# SENSORS.net
KiCad netlist of a schematic drawn in Altium Designer
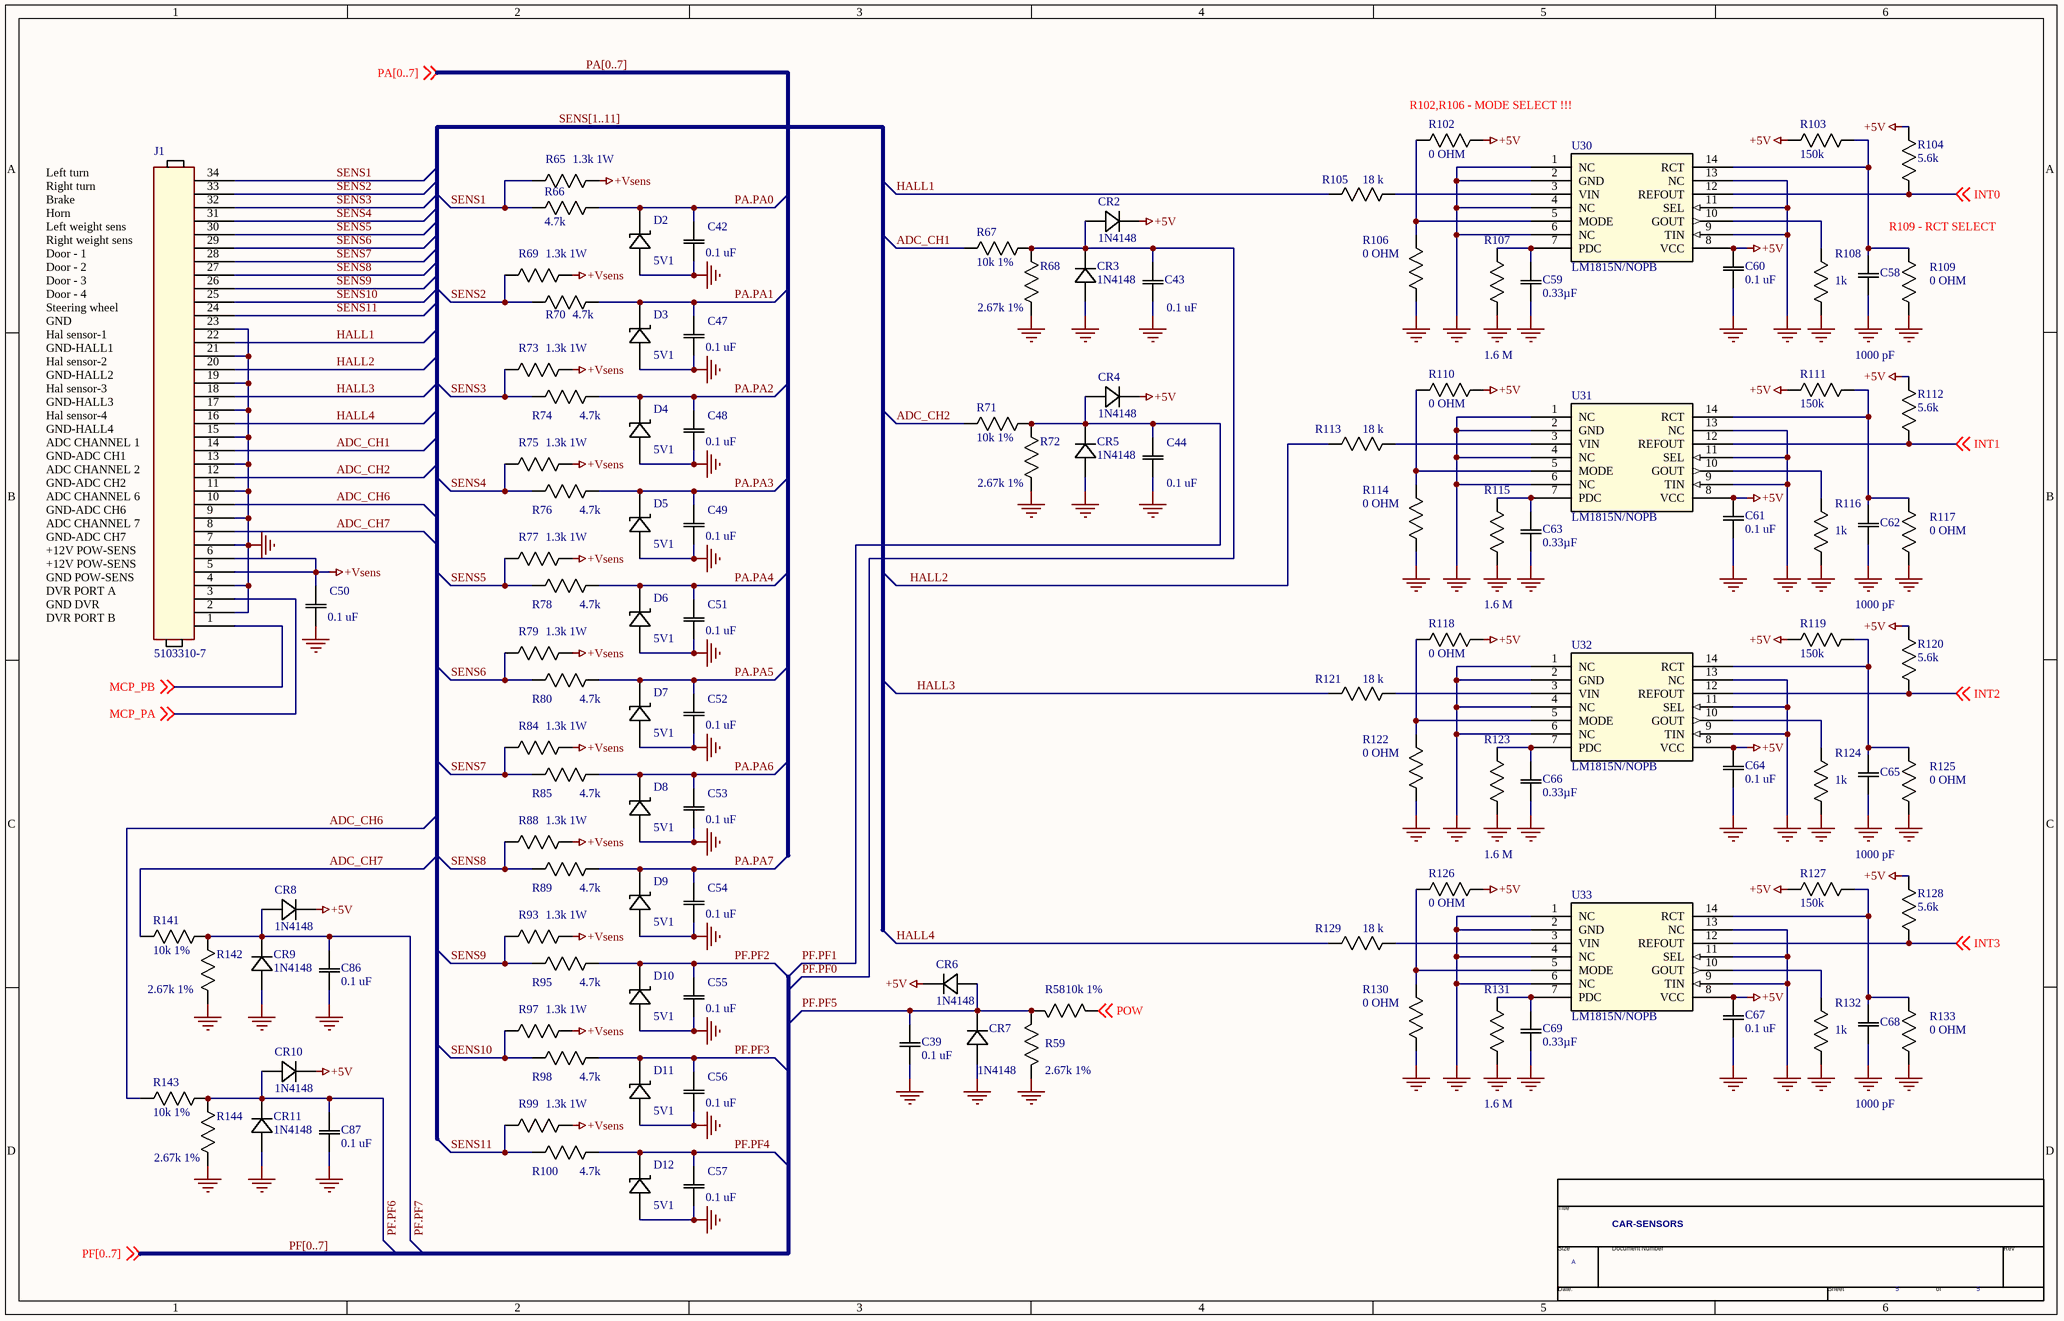
[diagram p0: SENSORS.SchDoc]

(export (version "E")
  (design (tool "Eeschema 10.0.6"))
  (components
    (comp (ref "C39")
      (value "0.1 uF")
      (footprint "SR20")
      (description "0.1µF ±10% 100V Ceramic Capacitor X7R Radial")
      (fields (field (name "MANUFACTURER_PART_NUMBER") "C320C104K1R5TA7301"))
      (libsource (lib "Discrete") (part "CAP RADIAL 2.54"))
    )
    (comp (ref "C42")
      (value "0.1 uF")
      (footprint "SR20")
      (description "0.1µF ±10% 100V Ceramic Capacitor X7R Radial")
      (fields (field (name "MANUFACTURER_PART_NUMBER") "C320C104K1R5TA7301"))
      (libsource (lib "Discrete") (part "CAP RADIAL 2.54"))
    )
    (comp (ref "C43")
      (value "0.1 uF")
      (footprint "SR20")
      (description "0.1µF ±10% 100V Ceramic Capacitor X7R Radial")
      (fields (field (name "MANUFACTURER_PART_NUMBER") "C320C104K1R5TA7301"))
      (libsource (lib "Discrete") (part "CAP RADIAL 2.54"))
    )
    (comp (ref "C44")
      (value "0.1 uF")
      (footprint "SR20")
      (description "0.1µF ±10% 100V Ceramic Capacitor X7R Radial")
      (fields (field (name "MANUFACTURER_PART_NUMBER") "C320C104K1R5TA7301"))
      (libsource (lib "Discrete") (part "CAP RADIAL 2.54"))
    )
    (comp (ref "C47")
      (value "0.1 uF")
      (footprint "SR20")
      (description "0.1µF ±10% 100V Ceramic Capacitor X7R Radial")
      (fields (field (name "MANUFACTURER_PART_NUMBER") "C320C104K1R5TA7301"))
      (libsource (lib "Discrete") (part "CAP RADIAL 2.54"))
    )
    (comp (ref "C48")
      (value "0.1 uF")
      (footprint "SR20")
      (description "0.1µF ±10% 100V Ceramic Capacitor X7R Radial")
      (fields (field (name "MANUFACTURER_PART_NUMBER") "C320C104K1R5TA7301"))
      (libsource (lib "Discrete") (part "CAP RADIAL 2.54"))
    )
    (comp (ref "C49")
      (value "0.1 uF")
      (footprint "SR20")
      (description "0.1µF ±10% 100V Ceramic Capacitor X7R Radial")
      (fields (field (name "MANUFACTURER_PART_NUMBER") "C320C104K1R5TA7301"))
      (libsource (lib "Discrete") (part "CAP RADIAL 2.54"))
    )
    (comp (ref "C50")
      (value "0.1 uF")
      (footprint "SR20")
      (description "0.1µF ±10% 100V Ceramic Capacitor X7R Radial")
      (fields (field (name "MANUFACTURER_PART_NUMBER") "C320C104K1R5TA7301"))
      (libsource (lib "Discrete") (part "CAP RADIAL 2.54"))
    )
    (comp (ref "C51")
      (value "0.1 uF")
      (footprint "SR20")
      (description "0.1µF ±10% 100V Ceramic Capacitor X7R Radial")
      (fields (field (name "MANUFACTURER_PART_NUMBER") "C320C104K1R5TA7301"))
      (libsource (lib "Discrete") (part "CAP RADIAL 2.54"))
    )
    (comp (ref "C52")
      (value "0.1 uF")
      (footprint "SR20")
      (description "0.1µF ±10% 100V Ceramic Capacitor X7R Radial")
      (fields (field (name "MANUFACTURER_PART_NUMBER") "C320C104K1R5TA7301"))
      (libsource (lib "Discrete") (part "CAP RADIAL 2.54"))
    )
    (comp (ref "C53")
      (value "0.1 uF")
      (footprint "SR20")
      (description "0.1µF ±10% 100V Ceramic Capacitor X7R Radial")
      (fields (field (name "MANUFACTURER_PART_NUMBER") "C320C104K1R5TA7301"))
      (libsource (lib "Discrete") (part "CAP RADIAL 2.54"))
    )
    (comp (ref "C54")
      (value "0.1 uF")
      (footprint "SR20")
      (description "0.1µF ±10% 100V Ceramic Capacitor X7R Radial")
      (fields (field (name "MANUFACTURER_PART_NUMBER") "C320C104K1R5TA7301"))
      (libsource (lib "Discrete") (part "CAP RADIAL 2.54"))
    )
    (comp (ref "C55")
      (value "0.1 uF")
      (footprint "SR20")
      (description "0.1µF ±10% 100V Ceramic Capacitor X7R Radial")
      (fields (field (name "MANUFACTURER_PART_NUMBER") "C320C104K1R5TA7301"))
      (libsource (lib "Discrete") (part "CAP RADIAL 2.54"))
    )
    (comp (ref "C56")
      (value "0.1 uF")
      (footprint "SR20")
      (description "0.1µF ±10% 100V Ceramic Capacitor X7R Radial")
      (fields (field (name "MANUFACTURER_PART_NUMBER") "C320C104K1R5TA7301"))
      (libsource (lib "Discrete") (part "CAP RADIAL 2.54"))
    )
    (comp (ref "C57")
      (value "0.1 uF")
      (footprint "SR20")
      (description "0.1µF ±10% 100V Ceramic Capacitor X7R Radial")
      (fields (field (name "MANUFACTURER_PART_NUMBER") "C320C104K1R5TA7301"))
      (libsource (lib "Discrete") (part "CAP RADIAL 2.54"))
    )
    (comp (ref "C58")
      (value "1000 pF")
      (footprint "SR20")
      (description "CAP CER 1000PF 50V X7R RADIAL")
      (fields (field (name "MANUFACTURER_PART_NUMBER") "C315C102K5R5TA7301"))
      (libsource (lib "Discrete") (part "CAP RADIAL 2.54"))
    )
    (comp (ref "C59")
      (value "0.33µF")
      (footprint "SR20")
      (description "CAP CER 0.33UF 50V X8R RADIAL")
      (fields (field (name "MANUFACTURER_PART_NUMBER") "AR205F334K4R"))
      (libsource (lib "Discrete") (part "CAP RADIAL 2.54"))
    )
    (comp (ref "C60")
      (value "0.1 uF")
      (footprint "SR20")
      (description "0.1µF ±10% 100V Ceramic Capacitor X7R Radial")
      (fields (field (name "MANUFACTURER_PART_NUMBER") "C320C104K1R5TA7301"))
      (libsource (lib "Discrete") (part "CAP RADIAL 2.54"))
    )
    (comp (ref "C61")
      (value "0.1 uF")
      (footprint "SR20")
      (description "0.1µF ±10% 100V Ceramic Capacitor X7R Radial")
      (fields (field (name "MANUFACTURER_PART_NUMBER") "C320C104K1R5TA7301"))
      (libsource (lib "Discrete") (part "CAP RADIAL 2.54"))
    )
    (comp (ref "C62")
      (value "1000 pF")
      (footprint "SR20")
      (description "CAP CER 1000PF 50V X7R RADIAL")
      (fields (field (name "MANUFACTURER_PART_NUMBER") "C315C102K5R5TA7301"))
      (libsource (lib "Discrete") (part "CAP RADIAL 2.54"))
    )
    (comp (ref "C63")
      (value "0.33µF")
      (footprint "SR20")
      (description "CAP CER 0.33UF 50V X8R RADIAL")
      (fields (field (name "MANUFACTURER_PART_NUMBER") "AR205F334K4R"))
      (libsource (lib "Discrete") (part "CAP RADIAL 2.54"))
    )
    (comp (ref "C64")
      (value "0.1 uF")
      (footprint "SR20")
      (description "0.1µF ±10% 100V Ceramic Capacitor X7R Radial")
      (fields (field (name "MANUFACTURER_PART_NUMBER") "C320C104K1R5TA7301"))
      (libsource (lib "Discrete") (part "CAP RADIAL 2.54"))
    )
    (comp (ref "C65")
      (value "1000 pF")
      (footprint "SR20")
      (description "CAP CER 1000PF 50V X7R RADIAL")
      (fields (field (name "MANUFACTURER_PART_NUMBER") "C315C102K5R5TA7301"))
      (libsource (lib "Discrete") (part "CAP RADIAL 2.54"))
    )
    (comp (ref "C66")
      (value "0.33µF")
      (footprint "SR20")
      (description "CAP CER 0.33UF 50V X8R RADIAL")
      (fields (field (name "MANUFACTURER_PART_NUMBER") "AR205F334K4R"))
      (libsource (lib "Discrete") (part "CAP RADIAL 2.54"))
    )
    (comp (ref "C67")
      (value "0.1 uF")
      (footprint "SR20")
      (description "0.1µF ±10% 100V Ceramic Capacitor X7R Radial")
      (fields (field (name "MANUFACTURER_PART_NUMBER") "C320C104K1R5TA7301"))
      (libsource (lib "Discrete") (part "CAP RADIAL 2.54"))
    )
    (comp (ref "C68")
      (value "1000 pF")
      (footprint "SR20")
      (description "CAP CER 1000PF 50V X7R RADIAL")
      (fields (field (name "MANUFACTURER_PART_NUMBER") "C315C102K5R5TA7301"))
      (libsource (lib "Discrete") (part "CAP RADIAL 2.54"))
    )
    (comp (ref "C69")
      (value "0.33µF")
      (footprint "SR20")
      (description "CAP CER 0.33UF 50V X8R RADIAL")
      (fields (field (name "MANUFACTURER_PART_NUMBER") "AR205F334K4R"))
      (libsource (lib "Discrete") (part "CAP RADIAL 2.54"))
    )
    (comp (ref "C86")
      (value "0.1 uF")
      (footprint "SR20")
      (description "0.1µF ±10% 100V Ceramic Capacitor X7R Radial")
      (fields (field (name "MANUFACTURER_PART_NUMBER") "C320C104K1R5TA7301"))
      (libsource (lib "Discrete") (part "CAP RADIAL 2.54"))
    )
    (comp (ref "C87")
      (value "0.1 uF")
      (footprint "SR20")
      (description "0.1µF ±10% 100V Ceramic Capacitor X7R Radial")
      (fields (field (name "MANUFACTURER_PART_NUMBER") "C320C104K1R5TA7301"))
      (libsource (lib "Discrete") (part "CAP RADIAL 2.54"))
    )
    (comp (ref "CR2")
      (value "1N4148")
      (footprint "DO35")
      (description "Imported")
      (fields (field (name "COPYRIGHT") "Copyright (C) 2016 Accelerated Designs. All rights reserved"))
      (libsource (lib "Discrete") (part "1N4148"))
    )
    (comp (ref "CR3")
      (value "1N4148")
      (footprint "DO35")
      (description "Imported")
      (fields (field (name "COPYRIGHT") "Copyright (C) 2016 Accelerated Designs. All rights reserved"))
      (libsource (lib "Discrete") (part "1N4148"))
    )
    (comp (ref "CR4")
      (value "1N4148")
      (footprint "DO35")
      (description "Imported")
      (fields (field (name "COPYRIGHT") "Copyright (C) 2016 Accelerated Designs. All rights reserved"))
      (libsource (lib "Discrete") (part "1N4148"))
    )
    (comp (ref "CR5")
      (value "1N4148")
      (footprint "DO35")
      (description "Imported")
      (fields (field (name "COPYRIGHT") "Copyright (C) 2016 Accelerated Designs. All rights reserved"))
      (libsource (lib "Discrete") (part "1N4148"))
    )
    (comp (ref "CR6")
      (value "1N4148")
      (footprint "DO35")
      (description "Imported")
      (fields (field (name "COPYRIGHT") "Copyright (C) 2016 Accelerated Designs. All rights reserved"))
      (libsource (lib "Discrete") (part "1N4148"))
    )
    (comp (ref "CR7")
      (value "1N4148")
      (footprint "DO35")
      (description "Imported")
      (fields (field (name "COPYRIGHT") "Copyright (C) 2016 Accelerated Designs. All rights reserved"))
      (libsource (lib "Discrete") (part "1N4148"))
    )
    (comp (ref "CR8")
      (value "1N4148")
      (footprint "DO35")
      (description "Imported")
      (fields (field (name "COPYRIGHT") "Copyright (C) 2016 Accelerated Designs. All rights reserved"))
      (libsource (lib "Discrete") (part "1N4148"))
    )
    (comp (ref "CR9")
      (value "1N4148")
      (footprint "DO35")
      (description "Imported")
      (fields (field (name "COPYRIGHT") "Copyright (C) 2016 Accelerated Designs. All rights reserved"))
      (libsource (lib "Discrete") (part "1N4148"))
    )
    (comp (ref "CR10")
      (value "1N4148")
      (footprint "DO35")
      (description "Imported")
      (fields (field (name "COPYRIGHT") "Copyright (C) 2016 Accelerated Designs. All rights reserved"))
      (libsource (lib "Discrete") (part "1N4148"))
    )
    (comp (ref "CR11")
      (value "1N4148")
      (footprint "DO35")
      (description "Imported")
      (fields (field (name "COPYRIGHT") "Copyright (C) 2016 Accelerated Designs. All rights reserved"))
      (libsource (lib "Discrete") (part "1N4148"))
    )
    (comp (ref "D2")
      (value "5V1")
      (footprint "DO35")
      (description "DIODE ZENER 5.1V 500MW DO35")
      (fields (field (name "MANUFACTURER_PART_NUMBER") "1N5231B"))
      (libsource (lib "Discrete") (part "ZENNER DO-35"))
    )
    (comp (ref "D3")
      (value "5V1")
      (footprint "DO35")
      (description "DIODE ZENER 5.1V 500MW DO35")
      (fields (field (name "MANUFACTURER_PART_NUMBER") "1N5231B"))
      (libsource (lib "Discrete") (part "ZENNER DO-35"))
    )
    (comp (ref "D4")
      (value "5V1")
      (footprint "DO35")
      (description "DIODE ZENER 5.1V 500MW DO35")
      (fields (field (name "MANUFACTURER_PART_NUMBER") "1N5231B"))
      (libsource (lib "Discrete") (part "ZENNER DO-35"))
    )
    (comp (ref "D5")
      (value "5V1")
      (footprint "DO35")
      (description "DIODE ZENER 5.1V 500MW DO35")
      (fields (field (name "MANUFACTURER_PART_NUMBER") "1N5231B"))
      (libsource (lib "Discrete") (part "ZENNER DO-35"))
    )
    (comp (ref "D6")
      (value "5V1")
      (footprint "DO35")
      (description "DIODE ZENER 5.1V 500MW DO35")
      (fields (field (name "MANUFACTURER_PART_NUMBER") "1N5231B"))
      (libsource (lib "Discrete") (part "ZENNER DO-35"))
    )
    (comp (ref "D7")
      (value "5V1")
      (footprint "DO35")
      (description "DIODE ZENER 5.1V 500MW DO35")
      (fields (field (name "MANUFACTURER_PART_NUMBER") "1N5231B"))
      (libsource (lib "Discrete") (part "ZENNER DO-35"))
    )
    (comp (ref "D8")
      (value "5V1")
      (footprint "DO35")
      (description "DIODE ZENER 5.1V 500MW DO35")
      (fields (field (name "MANUFACTURER_PART_NUMBER") "1N5231B"))
      (libsource (lib "Discrete") (part "ZENNER DO-35"))
    )
    (comp (ref "D9")
      (value "5V1")
      (footprint "DO35")
      (description "DIODE ZENER 5.1V 500MW DO35")
      (fields (field (name "MANUFACTURER_PART_NUMBER") "1N5231B"))
      (libsource (lib "Discrete") (part "ZENNER DO-35"))
    )
    (comp (ref "D10")
      (value "5V1")
      (footprint "DO35")
      (description "DIODE ZENER 5.1V 500MW DO35")
      (fields (field (name "MANUFACTURER_PART_NUMBER") "1N5231B"))
      (libsource (lib "Discrete") (part "ZENNER DO-35"))
    )
    (comp (ref "D11")
      (value "5V1")
      (footprint "DO35")
      (description "DIODE ZENER 5.1V 500MW DO35")
      (fields (field (name "MANUFACTURER_PART_NUMBER") "1N5231B"))
      (libsource (lib "Discrete") (part "ZENNER DO-35"))
    )
    (comp (ref "D12")
      (value "5V1")
      (footprint "DO35")
      (description "DIODE ZENER 5.1V 500MW DO35")
      (fields (field (name "MANUFACTURER_PART_NUMBER") "1N5231B"))
      (libsource (lib "Discrete") (part "ZENNER DO-35"))
    )
    (comp (ref "J1")
      (value "5103310-7")
      (footprint "*TYCO_5103310-7")
      (description "A/L LOW PRO HDR 34P RA BLACK")
      (libsource (lib "Connectors") (part "5103310-7"))
    )
    (comp (ref "R58")
      (value "10k 1%")
      (footprint "RES AXIAL 1/6W")
      (description "RES 10K OHM 1/8W 1% AXIAL")
      (fields (field (name "MANUFACTURER_PART_NUMBER") "RNF18FTD10K0"))
      (libsource (lib "Discrete") (part "Resistor Axial  1/6W"))
    )
    (comp (ref "R59")
      (value "2.67k 1%")
      (footprint "YAG_MF25")
      (description "RES 2.67K OHM 1/4W 1% AXIAL")
      (fields (field (name "MANUFACTURER_PART_NUMBER") "MFR-25FBF52-2K67"))
      (libsource (lib "Discrete") (part "Resistor Axial  1/4W"))
    )
    (comp (ref "R65")
      (value "1.3k 1W")
      (footprint "YAG_FMP100")
      (description "RES 1.3K OHM 1W 5% AXIAL")
      (fields (field (name "MANUFACTURER_PART_NUMBER") "RSF100JB-73-1K3"))
      (libsource (lib "Discrete") (part "Resistor Axial  1W"))
    )
    (comp (ref "R66")
      (value "4.7k")
      (footprint "RES AXIAL 1/6W")
      (description "RES 4.7K OHM 1/6W 5% AXIAL")
      (fields (field (name "MANUFACTURER_PART_NUMBER") "CFR-12JB-52-4K7"))
      (libsource (lib "Discrete") (part "Resistor Axial  1/6W"))
    )
    (comp (ref "R67")
      (value "10k 1%")
      (footprint "RES AXIAL 1/6W")
      (description "RES 10K OHM 1/8W 1% AXIAL")
      (fields (field (name "MANUFACTURER_PART_NUMBER") "RNF18FTD10K0"))
      (libsource (lib "Discrete") (part "Resistor Axial  1/6W"))
    )
    (comp (ref "R68")
      (value "2.67k 1%")
      (footprint "YAG_MF25")
      (description "RES 2.67K OHM 1/4W 1% AXIAL")
      (fields (field (name "MANUFACTURER_PART_NUMBER") "MFR-25FBF52-2K67"))
      (libsource (lib "Discrete") (part "Resistor Axial  1/4W"))
    )
    (comp (ref "R69")
      (value "1.3k 1W")
      (footprint "YAG_FMP100")
      (description "RES 1.3K OHM 1W 5% AXIAL")
      (fields (field (name "MANUFACTURER_PART_NUMBER") "RSF100JB-73-1K3"))
      (libsource (lib "Discrete") (part "Resistor Axial  1W"))
    )
    (comp (ref "R70")
      (value "4.7k")
      (footprint "RES AXIAL 1/6W")
      (description "RES 4.7K OHM 1/6W 5% AXIAL")
      (fields (field (name "MANUFACTURER_PART_NUMBER") "CFR-12JB-52-4K7"))
      (libsource (lib "Discrete") (part "Resistor Axial  1/6W"))
    )
    (comp (ref "R71")
      (value "10k 1%")
      (footprint "RES AXIAL 1/6W")
      (description "RES 10K OHM 1/8W 1% AXIAL")
      (fields (field (name "MANUFACTURER_PART_NUMBER") "RNF18FTD10K0"))
      (libsource (lib "Discrete") (part "Resistor Axial  1/6W"))
    )
    (comp (ref "R72")
      (value "2.67k 1%")
      (footprint "YAG_MF25")
      (description "RES 2.67K OHM 1/4W 1% AXIAL")
      (fields (field (name "MANUFACTURER_PART_NUMBER") "MFR-25FBF52-2K67"))
      (libsource (lib "Discrete") (part "Resistor Axial  1/4W"))
    )
    (comp (ref "R73")
      (value "1.3k 1W")
      (footprint "YAG_FMP100")
      (description "RES 1.3K OHM 1W 5% AXIAL")
      (fields (field (name "MANUFACTURER_PART_NUMBER") "RSF100JB-73-1K3"))
      (libsource (lib "Discrete") (part "Resistor Axial  1W"))
    )
    (comp (ref "R74")
      (value "4.7k")
      (footprint "RES AXIAL 1/6W")
      (description "RES 4.7K OHM 1/6W 5% AXIAL")
      (fields (field (name "MANUFACTURER_PART_NUMBER") "CFR-12JB-52-4K7"))
      (libsource (lib "Discrete") (part "Resistor Axial  1/6W"))
    )
    (comp (ref "R75")
      (value "1.3k 1W")
      (footprint "YAG_FMP100")
      (description "RES 1.3K OHM 1W 5% AXIAL")
      (fields (field (name "MANUFACTURER_PART_NUMBER") "RSF100JB-73-1K3"))
      (libsource (lib "Discrete") (part "Resistor Axial  1W"))
    )
    (comp (ref "R76")
      (value "4.7k")
      (footprint "RES AXIAL 1/6W")
      (description "RES 4.7K OHM 1/6W 5% AXIAL")
      (fields (field (name "MANUFACTURER_PART_NUMBER") "CFR-12JB-52-4K7"))
      (libsource (lib "Discrete") (part "Resistor Axial  1/6W"))
    )
    (comp (ref "R77")
      (value "1.3k 1W")
      (footprint "YAG_FMP100")
      (description "RES 1.3K OHM 1W 5% AXIAL")
      (fields (field (name "MANUFACTURER_PART_NUMBER") "RSF100JB-73-1K3"))
      (libsource (lib "Discrete") (part "Resistor Axial  1W"))
    )
    (comp (ref "R78")
      (value "4.7k")
      (footprint "RES AXIAL 1/6W")
      (description "RES 4.7K OHM 1/6W 5% AXIAL")
      (fields (field (name "MANUFACTURER_PART_NUMBER") "CFR-12JB-52-4K7"))
      (libsource (lib "Discrete") (part "Resistor Axial  1/6W"))
    )
    (comp (ref "R79")
      (value "1.3k 1W")
      (footprint "YAG_FMP100")
      (description "RES 1.3K OHM 1W 5% AXIAL")
      (fields (field (name "MANUFACTURER_PART_NUMBER") "RSF100JB-73-1K3"))
      (libsource (lib "Discrete") (part "Resistor Axial  1W"))
    )
    (comp (ref "R80")
      (value "4.7k")
      (footprint "RES AXIAL 1/6W")
      (description "RES 4.7K OHM 1/6W 5% AXIAL")
      (fields (field (name "MANUFACTURER_PART_NUMBER") "CFR-12JB-52-4K7"))
      (libsource (lib "Discrete") (part "Resistor Axial  1/6W"))
    )
    (comp (ref "R84")
      (value "1.3k 1W")
      (footprint "YAG_FMP100")
      (description "RES 1.3K OHM 1W 5% AXIAL")
      (fields (field (name "MANUFACTURER_PART_NUMBER") "RSF100JB-73-1K3"))
      (libsource (lib "Discrete") (part "Resistor Axial  1W"))
    )
    (comp (ref "R85")
      (value "4.7k")
      (footprint "RES AXIAL 1/6W")
      (description "RES 4.7K OHM 1/6W 5% AXIAL")
      (fields (field (name "MANUFACTURER_PART_NUMBER") "CFR-12JB-52-4K7"))
      (libsource (lib "Discrete") (part "Resistor Axial  1/6W"))
    )
    (comp (ref "R88")
      (value "1.3k 1W")
      (footprint "YAG_FMP100")
      (description "RES 1.3K OHM 1W 5% AXIAL")
      (fields (field (name "MANUFACTURER_PART_NUMBER") "RSF100JB-73-1K3"))
      (libsource (lib "Discrete") (part "Resistor Axial  1W"))
    )
    (comp (ref "R89")
      (value "4.7k")
      (footprint "RES AXIAL 1/6W")
      (description "RES 4.7K OHM 1/6W 5% AXIAL")
      (fields (field (name "MANUFACTURER_PART_NUMBER") "CFR-12JB-52-4K7"))
      (libsource (lib "Discrete") (part "Resistor Axial  1/6W"))
    )
    (comp (ref "R93")
      (value "1.3k 1W")
      (footprint "YAG_FMP100")
      (description "RES 1.3K OHM 1W 5% AXIAL")
      (fields (field (name "MANUFACTURER_PART_NUMBER") "RSF100JB-73-1K3"))
      (libsource (lib "Discrete") (part "Resistor Axial  1W"))
    )
    (comp (ref "R95")
      (value "4.7k")
      (footprint "RES AXIAL 1/6W")
      (description "RES 4.7K OHM 1/6W 5% AXIAL")
      (fields (field (name "MANUFACTURER_PART_NUMBER") "CFR-12JB-52-4K7"))
      (libsource (lib "Discrete") (part "Resistor Axial  1/6W"))
    )
    (comp (ref "R97")
      (value "1.3k 1W")
      (footprint "YAG_FMP100")
      (description "RES 1.3K OHM 1W 5% AXIAL")
      (fields (field (name "MANUFACTURER_PART_NUMBER") "RSF100JB-73-1K3"))
      (libsource (lib "Discrete") (part "Resistor Axial  1W"))
    )
    (comp (ref "R98")
      (value "4.7k")
      (footprint "RES AXIAL 1/6W")
      (description "RES 4.7K OHM 1/6W 5% AXIAL")
      (fields (field (name "MANUFACTURER_PART_NUMBER") "CFR-12JB-52-4K7"))
      (libsource (lib "Discrete") (part "Resistor Axial  1/6W"))
    )
    (comp (ref "R99")
      (value "1.3k 1W")
      (footprint "YAG_FMP100")
      (description "RES 1.3K OHM 1W 5% AXIAL")
      (fields (field (name "MANUFACTURER_PART_NUMBER") "RSF100JB-73-1K3"))
      (libsource (lib "Discrete") (part "Resistor Axial  1W"))
    )
    (comp (ref "R100")
      (value "4.7k")
      (footprint "RES AXIAL 1/6W")
      (description "RES 4.7K OHM 1/6W 5% AXIAL")
      (fields (field (name "MANUFACTURER_PART_NUMBER") "CFR-12JB-52-4K7"))
      (libsource (lib "Discrete") (part "Resistor Axial  1/6W"))
    )
    (comp (ref "R102")
      (value "0 OHM")
      (footprint "RES AXIAL 1/6W")
      (description "RES 0 OHM 1/6W JUMP AXIAL")
      (fields (field (name "MANUFACTURER_PART_NUMBER") "ZOR-12-B-52-0R"))
      (libsource (lib "Discrete") (part "Resistor Axial  1/6W"))
    )
    (comp (ref "R103")
      (value "150k")
      (footprint "RES AXIAL 1/6W")
      (description "RES 150K OHM 1/6W 5% AXIAL")
      (fields (field (name "MANUFACTURER_PART_NUMBER") "CFR-12JB-52-150K"))
      (libsource (lib "Discrete") (part "Resistor Axial  1/6W"))
    )
    (comp (ref "R104")
      (value "5.6k")
      (footprint "RES AXIAL 1/6W")
      (description "RES 5.6K OHM 1/6W 5% AXIAL")
      (fields (field (name "MANUFACTURER_PART_NUMBER") "CFR-12JB-52-5K6"))
      (libsource (lib "Discrete") (part "Resistor Axial  1/6W"))
    )
    (comp (ref "R105")
      (value "18 k")
      (footprint "RES AXIAL 1/6W")
      (description "RES 18K OHM 1/6W 5% AXIAL")
      (fields (field (name "MANUFACTURER_PART_NUMBER") "CFR-12JB-52-18K"))
      (libsource (lib "Discrete") (part "Resistor Axial  1/6W"))
    )
    (comp (ref "R106")
      (value "0 OHM")
      (footprint "RES AXIAL 1/6W")
      (description "RES 0 OHM 1/6W JUMP AXIAL")
      (fields (field (name "MANUFACTURER_PART_NUMBER") "ZOR-12-B-52-0R"))
      (libsource (lib "Discrete") (part "Resistor Axial  1/6W"))
    )
    (comp (ref "R107")
      (value "1.6 M")
      (footprint "RES AXIAL 1/6W")
      (description "RES 1.6M OHM 1/6W 5% AXIAL")
      (fields (field (name "MANUFACTURER_PART_NUMBER") "CFR-12JB-52-1M6"))
      (libsource (lib "Discrete") (part "Resistor Axial  1/6W"))
    )
    (comp (ref "R108")
      (value "1k")
      (footprint "RES AXIAL 1/6W")
      (description "RES 1K OHM 1/6W 5% AXIAL")
      (fields (field (name "MANUFACTURER_PART_NUMBER") "CFR-12JB-52-1K"))
      (libsource (lib "Discrete") (part "Resistor Axial  1/6W"))
    )
    (comp (ref "R109")
      (value "0 OHM")
      (footprint "RES AXIAL 1/6W")
      (description "RES 0 OHM 1/6W JUMP AXIAL")
      (fields (field (name "MANUFACTURER_PART_NUMBER") "ZOR-12-B-52-0R"))
      (libsource (lib "Discrete") (part "Resistor Axial  1/6W"))
    )
    (comp (ref "R110")
      (value "0 OHM")
      (footprint "RES AXIAL 1/6W")
      (description "RES 0 OHM 1/6W JUMP AXIAL")
      (fields (field (name "MANUFACTURER_PART_NUMBER") "ZOR-12-B-52-0R"))
      (libsource (lib "Discrete") (part "Resistor Axial  1/6W"))
    )
    (comp (ref "R111")
      (value "150k")
      (footprint "RES AXIAL 1/6W")
      (description "RES 150K OHM 1/6W 5% AXIAL")
      (fields (field (name "MANUFACTURER_PART_NUMBER") "CFR-12JB-52-150K"))
      (libsource (lib "Discrete") (part "Resistor Axial  1/6W"))
    )
    (comp (ref "R112")
      (value "5.6k")
      (footprint "RES AXIAL 1/6W")
      (description "RES 5.6K OHM 1/6W 5% AXIAL")
      (fields (field (name "MANUFACTURER_PART_NUMBER") "CFR-12JB-52-5K6"))
      (libsource (lib "Discrete") (part "Resistor Axial  1/6W"))
    )
    (comp (ref "R113")
      (value "18 k")
      (footprint "RES AXIAL 1/6W")
      (description "RES 18K OHM 1/6W 5% AXIAL")
      (fields (field (name "MANUFACTURER_PART_NUMBER") "CFR-12JB-52-18K"))
      (libsource (lib "Discrete") (part "Resistor Axial  1/6W"))
    )
    (comp (ref "R114")
      (value "0 OHM")
      (footprint "RES AXIAL 1/6W")
      (description "RES 0 OHM 1/6W JUMP AXIAL")
      (fields (field (name "MANUFACTURER_PART_NUMBER") "ZOR-12-B-52-0R"))
      (libsource (lib "Discrete") (part "Resistor Axial  1/6W"))
    )
    (comp (ref "R115")
      (value "1.6 M")
      (footprint "RES AXIAL 1/6W")
      (description "RES 1.6M OHM 1/6W 5% AXIAL")
      (fields (field (name "MANUFACTURER_PART_NUMBER") "CFR-12JB-52-1M6"))
      (libsource (lib "Discrete") (part "Resistor Axial  1/6W"))
    )
    (comp (ref "R116")
      (value "1k")
      (footprint "RES AXIAL 1/6W")
      (description "RES 1K OHM 1/6W 5% AXIAL")
      (fields (field (name "MANUFACTURER_PART_NUMBER") "CFR-12JB-52-1K"))
      (libsource (lib "Discrete") (part "Resistor Axial  1/6W"))
    )
    (comp (ref "R117")
      (value "0 OHM")
      (footprint "RES AXIAL 1/6W")
      (description "RES 0 OHM 1/6W JUMP AXIAL")
      (fields (field (name "MANUFACTURER_PART_NUMBER") "ZOR-12-B-52-0R"))
      (libsource (lib "Discrete") (part "Resistor Axial  1/6W"))
    )
    (comp (ref "R118")
      (value "0 OHM")
      (footprint "RES AXIAL 1/6W")
      (description "RES 0 OHM 1/6W JUMP AXIAL")
      (fields (field (name "MANUFACTURER_PART_NUMBER") "ZOR-12-B-52-0R"))
      (libsource (lib "Discrete") (part "Resistor Axial  1/6W"))
    )
    (comp (ref "R119")
      (value "150k")
      (footprint "RES AXIAL 1/6W")
      (description "RES 150K OHM 1/6W 5% AXIAL")
      (fields (field (name "MANUFACTURER_PART_NUMBER") "CFR-12JB-52-150K"))
      (libsource (lib "Discrete") (part "Resistor Axial  1/6W"))
    )
    (comp (ref "R120")
      (value "5.6k")
      (footprint "RES AXIAL 1/6W")
      (description "RES 5.6K OHM 1/6W 5% AXIAL")
      (fields (field (name "MANUFACTURER_PART_NUMBER") "CFR-12JB-52-5K6"))
      (libsource (lib "Discrete") (part "Resistor Axial  1/6W"))
    )
    (comp (ref "R121")
      (value "18 k")
      (footprint "RES AXIAL 1/6W")
      (description "RES 18K OHM 1/6W 5% AXIAL")
      (fields (field (name "MANUFACTURER_PART_NUMBER") "CFR-12JB-52-18K"))
      (libsource (lib "Discrete") (part "Resistor Axial  1/6W"))
    )
    (comp (ref "R122")
      (value "0 OHM")
      (footprint "RES AXIAL 1/6W")
      (description "RES 0 OHM 1/6W JUMP AXIAL")
      (fields (field (name "MANUFACTURER_PART_NUMBER") "ZOR-12-B-52-0R"))
      (libsource (lib "Discrete") (part "Resistor Axial  1/6W"))
    )
    (comp (ref "R123")
      (value "1.6 M")
      (footprint "RES AXIAL 1/6W")
      (description "RES 1.6M OHM 1/6W 5% AXIAL")
      (fields (field (name "MANUFACTURER_PART_NUMBER") "CFR-12JB-52-1M6"))
      (libsource (lib "Discrete") (part "Resistor Axial  1/6W"))
    )
    (comp (ref "R124")
      (value "1k")
      (footprint "RES AXIAL 1/6W")
      (description "RES 1K OHM 1/6W 5% AXIAL")
      (fields (field (name "MANUFACTURER_PART_NUMBER") "CFR-12JB-52-1K"))
      (libsource (lib "Discrete") (part "Resistor Axial  1/6W"))
    )
    (comp (ref "R125")
      (value "0 OHM")
      (footprint "RES AXIAL 1/6W")
      (description "RES 0 OHM 1/6W JUMP AXIAL")
      (fields (field (name "MANUFACTURER_PART_NUMBER") "ZOR-12-B-52-0R"))
      (libsource (lib "Discrete") (part "Resistor Axial  1/6W"))
    )
    (comp (ref "R126")
      (value "0 OHM")
      (footprint "RES AXIAL 1/6W")
      (description "RES 0 OHM 1/6W JUMP AXIAL")
      (fields (field (name "MANUFACTURER_PART_NUMBER") "ZOR-12-B-52-0R"))
      (libsource (lib "Discrete") (part "Resistor Axial  1/6W"))
    )
    (comp (ref "R127")
      (value "150k")
      (footprint "RES AXIAL 1/6W")
      (description "RES 150K OHM 1/6W 5% AXIAL")
      (fields (field (name "MANUFACTURER_PART_NUMBER") "CFR-12JB-52-150K"))
      (libsource (lib "Discrete") (part "Resistor Axial  1/6W"))
    )
    (comp (ref "R128")
      (value "5.6k")
      (footprint "RES AXIAL 1/6W")
      (description "RES 5.6K OHM 1/6W 5% AXIAL")
      (fields (field (name "MANUFACTURER_PART_NUMBER") "CFR-12JB-52-5K6"))
      (libsource (lib "Discrete") (part "Resistor Axial  1/6W"))
    )
    (comp (ref "R129")
      (value "18 k")
      (footprint "RES AXIAL 1/6W")
      (description "RES 18K OHM 1/6W 5% AXIAL")
      (fields (field (name "MANUFACTURER_PART_NUMBER") "CFR-12JB-52-18K"))
      (libsource (lib "Discrete") (part "Resistor Axial  1/6W"))
    )
    (comp (ref "R130")
      (value "0 OHM")
      (footprint "RES AXIAL 1/6W")
      (description "RES 0 OHM 1/6W JUMP AXIAL")
      (fields (field (name "MANUFACTURER_PART_NUMBER") "ZOR-12-B-52-0R"))
      (libsource (lib "Discrete") (part "Resistor Axial  1/6W"))
    )
    (comp (ref "R131")
      (value "1.6 M")
      (footprint "RES AXIAL 1/6W")
      (description "RES 1.6M OHM 1/6W 5% AXIAL")
      (fields (field (name "MANUFACTURER_PART_NUMBER") "CFR-12JB-52-1M6"))
      (libsource (lib "Discrete") (part "Resistor Axial  1/6W"))
    )
    (comp (ref "R132")
      (value "1k")
      (footprint "RES AXIAL 1/6W")
      (description "RES 1K OHM 1/6W 5% AXIAL")
      (fields (field (name "MANUFACTURER_PART_NUMBER") "CFR-12JB-52-1K"))
      (libsource (lib "Discrete") (part "Resistor Axial  1/6W"))
    )
    (comp (ref "R133")
      (value "0 OHM")
      (footprint "RES AXIAL 1/6W")
      (description "RES 0 OHM 1/6W JUMP AXIAL")
      (fields (field (name "MANUFACTURER_PART_NUMBER") "ZOR-12-B-52-0R"))
      (libsource (lib "Discrete") (part "Resistor Axial  1/6W"))
    )
    (comp (ref "R141")
      (value "10k 1%")
      (footprint "RES AXIAL 1/6W")
      (description "RES 10K OHM 1/8W 1% AXIAL")
      (fields (field (name "MANUFACTURER_PART_NUMBER") "RNF18FTD10K0"))
      (libsource (lib "Discrete") (part "Resistor Axial  1/6W"))
    )
    (comp (ref "R142")
      (value "2.67k 1%")
      (footprint "YAG_MF25")
      (description "RES 2.67K OHM 1/4W 1% AXIAL")
      (fields (field (name "MANUFACTURER_PART_NUMBER") "MFR-25FBF52-2K67"))
      (libsource (lib "Discrete") (part "Resistor Axial  1/4W"))
    )
    (comp (ref "R143")
      (value "10k 1%")
      (footprint "RES AXIAL 1/6W")
      (description "RES 10K OHM 1/8W 1% AXIAL")
      (fields (field (name "MANUFACTURER_PART_NUMBER") "RNF18FTD10K0"))
      (libsource (lib "Discrete") (part "Resistor Axial  1/6W"))
    )
    (comp (ref "R144")
      (value "2.67k 1%")
      (footprint "YAG_MF25")
      (description "RES 2.67K OHM 1/4W 1% AXIAL")
      (fields (field (name "MANUFACTURER_PART_NUMBER") "MFR-25FBF52-2K67"))
      (libsource (lib "Discrete") (part "Resistor Axial  1/4W"))
    )
    (comp (ref "U30")
      (value "LM1815N/NOPB")
      (footprint "PDIP14_300MC")
      (description "IC AMP ADAPTIVE SENSOR 14-DIP")
      (libsource (lib "ICs") (part "LM1815N/NOPB"))
    )
    (comp (ref "U31")
      (value "LM1815N/NOPB")
      (footprint "PDIP14_300MC")
      (description "IC AMP ADAPTIVE SENSOR 14-DIP")
      (libsource (lib "ICs") (part "LM1815N/NOPB"))
    )
    (comp (ref "U32")
      (value "LM1815N/NOPB")
      (footprint "PDIP14_300MC")
      (description "IC AMP ADAPTIVE SENSOR 14-DIP")
      (libsource (lib "ICs") (part "LM1815N/NOPB"))
    )
    (comp (ref "U33")
      (value "LM1815N/NOPB")
      (footprint "PDIP14_300MC")
      (description "IC AMP ADAPTIVE SENSOR 14-DIP")
      (libsource (lib "ICs") (part "LM1815N/NOPB"))
    )
  )
  (nets
    (net (code "1") (name "+5V") (class "Default")
      (node (ref "C60") (pin "2") (pinfunction "2_2") (pintype "passive"))
      (node (ref "C61") (pin "2") (pinfunction "2_2") (pintype "passive"))
      (node (ref "C64") (pin "2") (pinfunction "2_2") (pintype "passive"))
      (node (ref "C67") (pin "2") (pinfunction "2_2") (pintype "passive"))
      (node (ref "CR10") (pin "C") (pinfunction "C_C") (pintype "passive"))
      (node (ref "CR2") (pin "C") (pinfunction "C_C") (pintype "passive"))
      (node (ref "CR4") (pin "C") (pinfunction "C_C") (pintype "passive"))
      (node (ref "CR6") (pin "C") (pinfunction "C_C") (pintype "passive"))
      (node (ref "CR8") (pin "C") (pinfunction "C_C") (pintype "passive"))
      (node (ref "R102") (pin "2") (pinfunction "2_2") (pintype "passive"))
      (node (ref "R103") (pin "1") (pinfunction "1_1") (pintype "passive"))
      (node (ref "R104") (pin "1") (pinfunction "1_1") (pintype "passive"))
      (node (ref "R110") (pin "2") (pinfunction "2_2") (pintype "passive"))
      (node (ref "R111") (pin "1") (pinfunction "1_1") (pintype "passive"))
      (node (ref "R112") (pin "1") (pinfunction "1_1") (pintype "passive"))
      (node (ref "R118") (pin "2") (pinfunction "2_2") (pintype "passive"))
      (node (ref "R119") (pin "1") (pinfunction "1_1") (pintype "passive"))
      (node (ref "R120") (pin "1") (pinfunction "1_1") (pintype "passive"))
      (node (ref "R126") (pin "2") (pinfunction "2_2") (pintype "passive"))
      (node (ref "R127") (pin "1") (pinfunction "1_1") (pintype "passive"))
      (node (ref "R128") (pin "1") (pinfunction "1_1") (pintype "passive"))
      (node (ref "U30") (pin "8") (pinfunction "VCC_8") (pintype "power_in"))
      (node (ref "U31") (pin "8") (pinfunction "VCC_8") (pintype "power_in"))
      (node (ref "U32") (pin "8") (pinfunction "VCC_8") (pintype "power_in"))
      (node (ref "U33") (pin "8") (pinfunction "VCC_8") (pintype "power_in"))
    )
    (net (code "2") (name "+Vsens") (class "Default")
      (node (ref "C50") (pin "2") (pinfunction "2_2") (pintype "passive"))
      (node (ref "J1") (pin "5") (pinfunction "5_5") (pintype "passive"))
      (node (ref "J1") (pin "6") (pinfunction "6_6") (pintype "passive"))
      (node (ref "R65") (pin "1") (pinfunction "1_1") (pintype "passive"))
      (node (ref "R69") (pin "1") (pinfunction "1_1") (pintype "passive"))
      (node (ref "R73") (pin "1") (pinfunction "1_1") (pintype "passive"))
      (node (ref "R75") (pin "1") (pinfunction "1_1") (pintype "passive"))
      (node (ref "R77") (pin "1") (pinfunction "1_1") (pintype "passive"))
      (node (ref "R79") (pin "1") (pinfunction "1_1") (pintype "passive"))
      (node (ref "R84") (pin "1") (pinfunction "1_1") (pintype "passive"))
      (node (ref "R88") (pin "1") (pinfunction "1_1") (pintype "passive"))
      (node (ref "R93") (pin "1") (pinfunction "1_1") (pintype "passive"))
      (node (ref "R97") (pin "1") (pinfunction "1_1") (pintype "passive"))
      (node (ref "R99") (pin "1") (pinfunction "1_1") (pintype "passive"))
    )
    (net (code "3") (name "/ADC_CH1") (class "Default")
      (node (ref "J1") (pin "14") (pinfunction "14_14") (pintype "passive"))
      (node (ref "R67") (pin "1") (pinfunction "1_1") (pintype "passive"))
    )
    (net (code "4") (name "/ADC_CH2") (class "Default")
      (node (ref "J1") (pin "12") (pinfunction "12_12") (pintype "passive"))
      (node (ref "R71") (pin "1") (pinfunction "1_1") (pintype "passive"))
    )
    (net (code "5") (name "/ADC_CH6") (class "Default")
      (node (ref "J1") (pin "10") (pinfunction "10_10") (pintype "passive"))
      (node (ref "R143") (pin "1") (pinfunction "1_1") (pintype "passive"))
    )
    (net (code "6") (name "/ADC_CH7") (class "Default")
      (node (ref "J1") (pin "8") (pinfunction "8_8") (pintype "passive"))
      (node (ref "R141") (pin "1") (pinfunction "1_1") (pintype "passive"))
    )
    (net (code "7") (name "/HALL1") (class "Default")
      (node (ref "J1") (pin "22") (pinfunction "22_22") (pintype "passive"))
      (node (ref "R105") (pin "2") (pinfunction "2_2") (pintype "passive"))
    )
    (net (code "8") (name "/HALL2") (class "Default")
      (node (ref "J1") (pin "20") (pinfunction "20_20") (pintype "passive"))
      (node (ref "R113") (pin "2") (pinfunction "2_2") (pintype "passive"))
    )
    (net (code "9") (name "/HALL3") (class "Default")
      (node (ref "J1") (pin "18") (pinfunction "18_18") (pintype "passive"))
      (node (ref "R121") (pin "2") (pinfunction "2_2") (pintype "passive"))
    )
    (net (code "10") (name "/HALL4") (class "Default")
      (node (ref "J1") (pin "16") (pinfunction "16_16") (pintype "passive"))
      (node (ref "R129") (pin "2") (pinfunction "2_2") (pintype "passive"))
    )
    (net (code "11") (name "/PA.PA0") (class "Default")
      (node (ref "C42") (pin "2") (pinfunction "2_2") (pintype "passive"))
      (node (ref "D2") (pin "C") (pinfunction "C_C") (pintype "passive"))
      (node (ref "R66") (pin "1") (pinfunction "1_1") (pintype "passive"))
    )
    (net (code "12") (name "/PA.PA1") (class "Default")
      (node (ref "C47") (pin "2") (pinfunction "2_2") (pintype "passive"))
      (node (ref "D3") (pin "C") (pinfunction "C_C") (pintype "passive"))
      (node (ref "R70") (pin "1") (pinfunction "1_1") (pintype "passive"))
    )
    (net (code "13") (name "/PA.PA2") (class "Default")
      (node (ref "C48") (pin "2") (pinfunction "2_2") (pintype "passive"))
      (node (ref "D4") (pin "C") (pinfunction "C_C") (pintype "passive"))
      (node (ref "R74") (pin "1") (pinfunction "1_1") (pintype "passive"))
    )
    (net (code "14") (name "/PA.PA3") (class "Default")
      (node (ref "C49") (pin "2") (pinfunction "2_2") (pintype "passive"))
      (node (ref "D5") (pin "C") (pinfunction "C_C") (pintype "passive"))
      (node (ref "R76") (pin "1") (pinfunction "1_1") (pintype "passive"))
    )
    (net (code "15") (name "/PA.PA4") (class "Default")
      (node (ref "C51") (pin "2") (pinfunction "2_2") (pintype "passive"))
      (node (ref "D6") (pin "C") (pinfunction "C_C") (pintype "passive"))
      (node (ref "R78") (pin "1") (pinfunction "1_1") (pintype "passive"))
    )
    (net (code "16") (name "/PA.PA5") (class "Default")
      (node (ref "C52") (pin "2") (pinfunction "2_2") (pintype "passive"))
      (node (ref "D7") (pin "C") (pinfunction "C_C") (pintype "passive"))
      (node (ref "R80") (pin "1") (pinfunction "1_1") (pintype "passive"))
    )
    (net (code "17") (name "/PA.PA6") (class "Default")
      (node (ref "C53") (pin "2") (pinfunction "2_2") (pintype "passive"))
      (node (ref "D8") (pin "C") (pinfunction "C_C") (pintype "passive"))
      (node (ref "R85") (pin "1") (pinfunction "1_1") (pintype "passive"))
    )
    (net (code "18") (name "/PA.PA7") (class "Default")
      (node (ref "C54") (pin "2") (pinfunction "2_2") (pintype "passive"))
      (node (ref "D9") (pin "C") (pinfunction "C_C") (pintype "passive"))
      (node (ref "R89") (pin "1") (pinfunction "1_1") (pintype "passive"))
    )
    (net (code "19") (name "/PF.PF0") (class "Default")
      (node (ref "C43") (pin "2") (pinfunction "2_2") (pintype "passive"))
      (node (ref "CR2") (pin "A") (pinfunction "A_A") (pintype "passive"))
      (node (ref "CR3") (pin "C") (pinfunction "C_C") (pintype "passive"))
      (node (ref "R67") (pin "2") (pinfunction "2_2") (pintype "passive"))
      (node (ref "R68") (pin "2") (pinfunction "2_2") (pintype "passive"))
    )
    (net (code "20") (name "/PF.PF1") (class "Default")
      (node (ref "C44") (pin "2") (pinfunction "2_2") (pintype "passive"))
      (node (ref "CR4") (pin "A") (pinfunction "A_A") (pintype "passive"))
      (node (ref "CR5") (pin "C") (pinfunction "C_C") (pintype "passive"))
      (node (ref "R71") (pin "2") (pinfunction "2_2") (pintype "passive"))
      (node (ref "R72") (pin "2") (pinfunction "2_2") (pintype "passive"))
    )
    (net (code "21") (name "/PF.PF2") (class "Default")
      (node (ref "C55") (pin "2") (pinfunction "2_2") (pintype "passive"))
      (node (ref "D10") (pin "C") (pinfunction "C_C") (pintype "passive"))
      (node (ref "R95") (pin "1") (pinfunction "1_1") (pintype "passive"))
    )
    (net (code "22") (name "/PF.PF3") (class "Default")
      (node (ref "C56") (pin "2") (pinfunction "2_2") (pintype "passive"))
      (node (ref "D11") (pin "C") (pinfunction "C_C") (pintype "passive"))
      (node (ref "R98") (pin "1") (pinfunction "1_1") (pintype "passive"))
    )
    (net (code "23") (name "/PF.PF4") (class "Default")
      (node (ref "C57") (pin "2") (pinfunction "2_2") (pintype "passive"))
      (node (ref "D12") (pin "C") (pinfunction "C_C") (pintype "passive"))
      (node (ref "R100") (pin "1") (pinfunction "1_1") (pintype "passive"))
    )
    (net (code "24") (name "/PF.PF5") (class "Default")
      (node (ref "C39") (pin "2") (pinfunction "2_2") (pintype "passive"))
      (node (ref "CR6") (pin "A") (pinfunction "A_A") (pintype "passive"))
      (node (ref "CR7") (pin "C") (pinfunction "C_C") (pintype "passive"))
      (node (ref "R58") (pin "2") (pinfunction "2_2") (pintype "passive"))
      (node (ref "R59") (pin "2") (pinfunction "2_2") (pintype "passive"))
    )
    (net (code "25") (name "/PF.PF6") (class "Default")
      (node (ref "C87") (pin "2") (pinfunction "2_2") (pintype "passive"))
      (node (ref "CR10") (pin "A") (pinfunction "A_A") (pintype "passive"))
      (node (ref "CR11") (pin "C") (pinfunction "C_C") (pintype "passive"))
      (node (ref "R143") (pin "2") (pinfunction "2_2") (pintype "passive"))
      (node (ref "R144") (pin "2") (pinfunction "2_2") (pintype "passive"))
    )
    (net (code "26") (name "/PF.PF7") (class "Default")
      (node (ref "C86") (pin "2") (pinfunction "2_2") (pintype "passive"))
      (node (ref "CR8") (pin "A") (pinfunction "A_A") (pintype "passive"))
      (node (ref "CR9") (pin "C") (pinfunction "C_C") (pintype "passive"))
      (node (ref "R141") (pin "2") (pinfunction "2_2") (pintype "passive"))
      (node (ref "R142") (pin "2") (pinfunction "2_2") (pintype "passive"))
    )
    (net (code "27") (name "/SENS1") (class "Default")
      (node (ref "J1") (pin "34") (pinfunction "34_34") (pintype "passive"))
      (node (ref "R65") (pin "2") (pinfunction "2_2") (pintype "passive"))
      (node (ref "R66") (pin "2") (pinfunction "2_2") (pintype "passive"))
    )
    (net (code "28") (name "/SENS2") (class "Default")
      (node (ref "J1") (pin "33") (pinfunction "33_33") (pintype "passive"))
      (node (ref "R69") (pin "2") (pinfunction "2_2") (pintype "passive"))
      (node (ref "R70") (pin "2") (pinfunction "2_2") (pintype "passive"))
    )
    (net (code "29") (name "/SENS3") (class "Default")
      (node (ref "J1") (pin "32") (pinfunction "32_32") (pintype "passive"))
      (node (ref "R73") (pin "2") (pinfunction "2_2") (pintype "passive"))
      (node (ref "R74") (pin "2") (pinfunction "2_2") (pintype "passive"))
    )
    (net (code "30") (name "/SENS4") (class "Default")
      (node (ref "J1") (pin "31") (pinfunction "31_31") (pintype "passive"))
      (node (ref "R75") (pin "2") (pinfunction "2_2") (pintype "passive"))
      (node (ref "R76") (pin "2") (pinfunction "2_2") (pintype "passive"))
    )
    (net (code "31") (name "/SENS5") (class "Default")
      (node (ref "J1") (pin "30") (pinfunction "30_30") (pintype "passive"))
      (node (ref "R77") (pin "2") (pinfunction "2_2") (pintype "passive"))
      (node (ref "R78") (pin "2") (pinfunction "2_2") (pintype "passive"))
    )
    (net (code "32") (name "/SENS6") (class "Default")
      (node (ref "J1") (pin "29") (pinfunction "29_29") (pintype "passive"))
      (node (ref "R79") (pin "2") (pinfunction "2_2") (pintype "passive"))
      (node (ref "R80") (pin "2") (pinfunction "2_2") (pintype "passive"))
    )
    (net (code "33") (name "/SENS7") (class "Default")
      (node (ref "J1") (pin "28") (pinfunction "28_28") (pintype "passive"))
      (node (ref "R84") (pin "2") (pinfunction "2_2") (pintype "passive"))
      (node (ref "R85") (pin "2") (pinfunction "2_2") (pintype "passive"))
    )
    (net (code "34") (name "/SENS8") (class "Default")
      (node (ref "J1") (pin "27") (pinfunction "27_27") (pintype "passive"))
      (node (ref "R88") (pin "2") (pinfunction "2_2") (pintype "passive"))
      (node (ref "R89") (pin "2") (pinfunction "2_2") (pintype "passive"))
    )
    (net (code "35") (name "/SENS9") (class "Default")
      (node (ref "J1") (pin "26") (pinfunction "26_26") (pintype "passive"))
      (node (ref "R93") (pin "2") (pinfunction "2_2") (pintype "passive"))
      (node (ref "R95") (pin "2") (pinfunction "2_2") (pintype "passive"))
    )
    (net (code "36") (name "/SENS10") (class "Default")
      (node (ref "J1") (pin "25") (pinfunction "25_25") (pintype "passive"))
      (node (ref "R97") (pin "2") (pinfunction "2_2") (pintype "passive"))
      (node (ref "R98") (pin "2") (pinfunction "2_2") (pintype "passive"))
    )
    (net (code "37") (name "/SENS11") (class "Default")
      (node (ref "J1") (pin "24") (pinfunction "24_24") (pintype "passive"))
      (node (ref "R100") (pin "2") (pinfunction "2_2") (pintype "passive"))
      (node (ref "R99") (pin "2") (pinfunction "2_2") (pintype "passive"))
    )
    (net (code "39") (name "GND") (class "Default")
      (node (ref "C39") (pin "1") (pinfunction "1_1") (pintype "passive"))
      (node (ref "C42") (pin "1") (pinfunction "1_1") (pintype "passive"))
      (node (ref "C43") (pin "1") (pinfunction "1_1") (pintype "passive"))
      (node (ref "C44") (pin "1") (pinfunction "1_1") (pintype "passive"))
      (node (ref "C47") (pin "1") (pinfunction "1_1") (pintype "passive"))
      (node (ref "C48") (pin "1") (pinfunction "1_1") (pintype "passive"))
      (node (ref "C49") (pin "1") (pinfunction "1_1") (pintype "passive"))
      (node (ref "C50") (pin "1") (pinfunction "1_1") (pintype "passive"))
      (node (ref "C51") (pin "1") (pinfunction "1_1") (pintype "passive"))
      (node (ref "C52") (pin "1") (pinfunction "1_1") (pintype "passive"))
      (node (ref "C53") (pin "1") (pinfunction "1_1") (pintype "passive"))
      (node (ref "C54") (pin "1") (pinfunction "1_1") (pintype "passive"))
      (node (ref "C55") (pin "1") (pinfunction "1_1") (pintype "passive"))
      (node (ref "C56") (pin "1") (pinfunction "1_1") (pintype "passive"))
      (node (ref "C57") (pin "1") (pinfunction "1_1") (pintype "passive"))
      (node (ref "C58") (pin "1") (pinfunction "1_1") (pintype "passive"))
      (node (ref "C59") (pin "1") (pinfunction "1_1") (pintype "passive"))
      (node (ref "C60") (pin "1") (pinfunction "1_1") (pintype "passive"))
      (node (ref "C61") (pin "1") (pinfunction "1_1") (pintype "passive"))
      (node (ref "C62") (pin "1") (pinfunction "1_1") (pintype "passive"))
      (node (ref "C63") (pin "1") (pinfunction "1_1") (pintype "passive"))
      (node (ref "C64") (pin "1") (pinfunction "1_1") (pintype "passive"))
      (node (ref "C65") (pin "1") (pinfunction "1_1") (pintype "passive"))
      (node (ref "C66") (pin "1") (pinfunction "1_1") (pintype "passive"))
      (node (ref "C67") (pin "1") (pinfunction "1_1") (pintype "passive"))
      (node (ref "C68") (pin "1") (pinfunction "1_1") (pintype "passive"))
      (node (ref "C69") (pin "1") (pinfunction "1_1") (pintype "passive"))
      (node (ref "C86") (pin "1") (pinfunction "1_1") (pintype "passive"))
      (node (ref "C87") (pin "1") (pinfunction "1_1") (pintype "passive"))
      (node (ref "CR11") (pin "A") (pinfunction "A_A") (pintype "passive"))
      (node (ref "CR3") (pin "A") (pinfunction "A_A") (pintype "passive"))
      (node (ref "CR5") (pin "A") (pinfunction "A_A") (pintype "passive"))
      (node (ref "CR7") (pin "A") (pinfunction "A_A") (pintype "passive"))
      (node (ref "CR9") (pin "A") (pinfunction "A_A") (pintype "passive"))
      (node (ref "D10") (pin "A") (pinfunction "A_A") (pintype "passive"))
      (node (ref "D11") (pin "A") (pinfunction "A_A") (pintype "passive"))
      (node (ref "D12") (pin "A") (pinfunction "A_A") (pintype "passive"))
      (node (ref "D2") (pin "A") (pinfunction "A_A") (pintype "passive"))
      (node (ref "D3") (pin "A") (pinfunction "A_A") (pintype "passive"))
      (node (ref "D4") (pin "A") (pinfunction "A_A") (pintype "passive"))
      (node (ref "D5") (pin "A") (pinfunction "A_A") (pintype "passive"))
      (node (ref "D6") (pin "A") (pinfunction "A_A") (pintype "passive"))
      (node (ref "D7") (pin "A") (pinfunction "A_A") (pintype "passive"))
      (node (ref "D8") (pin "A") (pinfunction "A_A") (pintype "passive"))
      (node (ref "D9") (pin "A") (pinfunction "A_A") (pintype "passive"))
      (node (ref "J1") (pin "11") (pinfunction "11_11") (pintype "passive"))
      (node (ref "J1") (pin "13") (pinfunction "13_13") (pintype "passive"))
      (node (ref "J1") (pin "15") (pinfunction "15_15") (pintype "passive"))
      (node (ref "J1") (pin "17") (pinfunction "17_17") (pintype "passive"))
      (node (ref "J1") (pin "19") (pinfunction "19_19") (pintype "passive"))
      (node (ref "J1") (pin "2") (pinfunction "2_2") (pintype "passive"))
      (node (ref "J1") (pin "21") (pinfunction "21_21") (pintype "passive"))
      (node (ref "J1") (pin "23") (pinfunction "23_23") (pintype "passive"))
      (node (ref "J1") (pin "4") (pinfunction "4_4") (pintype "passive"))
      (node (ref "J1") (pin "7") (pinfunction "7_7") (pintype "passive"))
      (node (ref "J1") (pin "9") (pinfunction "9_9") (pintype "passive"))
      (node (ref "R106") (pin "1") (pinfunction "1_1") (pintype "passive"))
      (node (ref "R107") (pin "2") (pinfunction "2_2") (pintype "passive"))
      (node (ref "R108") (pin "1") (pinfunction "1_1") (pintype "passive"))
      (node (ref "R109") (pin "1") (pinfunction "1_1") (pintype "passive"))
      (node (ref "R114") (pin "1") (pinfunction "1_1") (pintype "passive"))
      (node (ref "R115") (pin "2") (pinfunction "2_2") (pintype "passive"))
      (node (ref "R116") (pin "1") (pinfunction "1_1") (pintype "passive"))
      (node (ref "R117") (pin "1") (pinfunction "1_1") (pintype "passive"))
      (node (ref "R122") (pin "1") (pinfunction "1_1") (pintype "passive"))
      (node (ref "R123") (pin "2") (pinfunction "2_2") (pintype "passive"))
      (node (ref "R124") (pin "1") (pinfunction "1_1") (pintype "passive"))
      (node (ref "R125") (pin "1") (pinfunction "1_1") (pintype "passive"))
      (node (ref "R130") (pin "1") (pinfunction "1_1") (pintype "passive"))
      (node (ref "R131") (pin "2") (pinfunction "2_2") (pintype "passive"))
      (node (ref "R132") (pin "1") (pinfunction "1_1") (pintype "passive"))
      (node (ref "R133") (pin "1") (pinfunction "1_1") (pintype "passive"))
      (node (ref "R142") (pin "1") (pinfunction "1_1") (pintype "passive"))
      (node (ref "R144") (pin "1") (pinfunction "1_1") (pintype "passive"))
      (node (ref "R59") (pin "1") (pinfunction "1_1") (pintype "passive"))
      (node (ref "R68") (pin "1") (pinfunction "1_1") (pintype "passive"))
      (node (ref "R72") (pin "1") (pinfunction "1_1") (pintype "passive"))
      (node (ref "U30") (pin "1") (pinfunction "NC_1") (pintype "passive"))
      (node (ref "U30") (pin "11") (pinfunction "SEL_11") (pintype "input"))
      (node (ref "U30") (pin "13") (pinfunction "NC_13") (pintype "passive"))
      (node (ref "U30") (pin "2") (pinfunction "GND_2") (pintype "power_in"))
      (node (ref "U30") (pin "4") (pinfunction "NC_4") (pintype "passive"))
      (node (ref "U30") (pin "6") (pinfunction "NC_6") (pintype "passive"))
      (node (ref "U30") (pin "9") (pinfunction "TIN_9") (pintype "input"))
      (node (ref "U31") (pin "1") (pinfunction "NC_1") (pintype "passive"))
      (node (ref "U31") (pin "11") (pinfunction "SEL_11") (pintype "input"))
      (node (ref "U31") (pin "13") (pinfunction "NC_13") (pintype "passive"))
      (node (ref "U31") (pin "2") (pinfunction "GND_2") (pintype "power_in"))
      (node (ref "U31") (pin "4") (pinfunction "NC_4") (pintype "passive"))
      (node (ref "U31") (pin "6") (pinfunction "NC_6") (pintype "passive"))
      (node (ref "U31") (pin "9") (pinfunction "TIN_9") (pintype "input"))
      (node (ref "U32") (pin "1") (pinfunction "NC_1") (pintype "passive"))
      (node (ref "U32") (pin "11") (pinfunction "SEL_11") (pintype "input"))
      (node (ref "U32") (pin "13") (pinfunction "NC_13") (pintype "passive"))
      (node (ref "U32") (pin "2") (pinfunction "GND_2") (pintype "power_in"))
      (node (ref "U32") (pin "4") (pinfunction "NC_4") (pintype "passive"))
      (node (ref "U32") (pin "6") (pinfunction "NC_6") (pintype "passive"))
      (node (ref "U32") (pin "9") (pinfunction "TIN_9") (pintype "input"))
      (node (ref "U33") (pin "1") (pinfunction "NC_1") (pintype "passive"))
      (node (ref "U33") (pin "11") (pinfunction "SEL_11") (pintype "input"))
      (node (ref "U33") (pin "13") (pinfunction "NC_13") (pintype "passive"))
      (node (ref "U33") (pin "2") (pinfunction "GND_2") (pintype "power_in"))
      (node (ref "U33") (pin "4") (pinfunction "NC_4") (pintype "passive"))
      (node (ref "U33") (pin "6") (pinfunction "NC_6") (pintype "passive"))
      (node (ref "U33") (pin "9") (pinfunction "TIN_9") (pintype "input"))
    )
    (net (code "40") (name "INT0") (class "Default")
      (node (ref "R104") (pin "2") (pinfunction "2_2") (pintype "passive"))
      (node (ref "U30") (pin "12") (pinfunction "REFOUT_12") (pintype "passive"))
    )
    (net (code "41") (name "INT1") (class "Default")
      (node (ref "R112") (pin "2") (pinfunction "2_2") (pintype "passive"))
      (node (ref "U31") (pin "12") (pinfunction "REFOUT_12") (pintype "passive"))
    )
    (net (code "42") (name "INT2") (class "Default")
      (node (ref "R120") (pin "2") (pinfunction "2_2") (pintype "passive"))
      (node (ref "U32") (pin "12") (pinfunction "REFOUT_12") (pintype "passive"))
    )
    (net (code "43") (name "INT3") (class "Default")
      (node (ref "R128") (pin "2") (pinfunction "2_2") (pintype "passive"))
      (node (ref "U33") (pin "12") (pinfunction "REFOUT_12") (pintype "passive"))
    )
    (net (code "44") (name "MCP_PA") (class "Default")
      (node (ref "J1") (pin "3") (pinfunction "3_3") (pintype "passive"))
    )
    (net (code "45") (name "MCP_PB") (class "Default")
      (node (ref "J1") (pin "1") (pinfunction "1_1") (pintype "passive"))
    )
    (net (code "46") (name "Net-(U30-GOUT)") (class "Default")
      (node (ref "R108") (pin "2") (pinfunction "2_2") (pintype "passive"))
      (node (ref "U30") (pin "10") (pinfunction "GOUT_10") (pintype "output"))
    )
    (net (code "47") (name "Net-(U30-MODE)") (class "Default")
      (node (ref "R102") (pin "1") (pinfunction "1_1") (pintype "passive"))
      (node (ref "R106") (pin "2") (pinfunction "2_2") (pintype "passive"))
      (node (ref "U30") (pin "5") (pinfunction "MODE_5") (pintype "passive"))
    )
    (net (code "48") (name "Net-(U30-PDC)") (class "Default")
      (node (ref "C59") (pin "2") (pinfunction "2_2") (pintype "passive"))
      (node (ref "R107") (pin "1") (pinfunction "1_1") (pintype "passive"))
      (node (ref "U30") (pin "7") (pinfunction "PDC_7") (pintype "passive"))
    )
    (net (code "49") (name "Net-(U30-RCT)") (class "Default")
      (node (ref "C58") (pin "2") (pinfunction "2_2") (pintype "passive"))
      (node (ref "R103") (pin "2") (pinfunction "2_2") (pintype "passive"))
      (node (ref "R109") (pin "2") (pinfunction "2_2") (pintype "passive"))
      (node (ref "U30") (pin "14") (pinfunction "RCT_14") (pintype "passive"))
    )
    (net (code "50") (name "Net-(U30-VIN)") (class "Default")
      (node (ref "R105") (pin "1") (pinfunction "1_1") (pintype "passive"))
      (node (ref "U30") (pin "3") (pinfunction "VIN_3") (pintype "power_in"))
    )
    (net (code "51") (name "Net-(U31-GOUT)") (class "Default")
      (node (ref "R116") (pin "2") (pinfunction "2_2") (pintype "passive"))
      (node (ref "U31") (pin "10") (pinfunction "GOUT_10") (pintype "output"))
    )
    (net (code "52") (name "Net-(U31-MODE)") (class "Default")
      (node (ref "R110") (pin "1") (pinfunction "1_1") (pintype "passive"))
      (node (ref "R114") (pin "2") (pinfunction "2_2") (pintype "passive"))
      (node (ref "U31") (pin "5") (pinfunction "MODE_5") (pintype "passive"))
    )
    (net (code "53") (name "Net-(U31-PDC)") (class "Default")
      (node (ref "C63") (pin "2") (pinfunction "2_2") (pintype "passive"))
      (node (ref "R115") (pin "1") (pinfunction "1_1") (pintype "passive"))
      (node (ref "U31") (pin "7") (pinfunction "PDC_7") (pintype "passive"))
    )
    (net (code "54") (name "Net-(U31-RCT)") (class "Default")
      (node (ref "C62") (pin "2") (pinfunction "2_2") (pintype "passive"))
      (node (ref "R111") (pin "2") (pinfunction "2_2") (pintype "passive"))
      (node (ref "R117") (pin "2") (pinfunction "2_2") (pintype "passive"))
      (node (ref "U31") (pin "14") (pinfunction "RCT_14") (pintype "passive"))
    )
    (net (code "55") (name "Net-(U31-VIN)") (class "Default")
      (node (ref "R113") (pin "1") (pinfunction "1_1") (pintype "passive"))
      (node (ref "U31") (pin "3") (pinfunction "VIN_3") (pintype "power_in"))
    )
    (net (code "56") (name "Net-(U32-GOUT)") (class "Default")
      (node (ref "R124") (pin "2") (pinfunction "2_2") (pintype "passive"))
      (node (ref "U32") (pin "10") (pinfunction "GOUT_10") (pintype "output"))
    )
    (net (code "57") (name "Net-(U32-MODE)") (class "Default")
      (node (ref "R118") (pin "1") (pinfunction "1_1") (pintype "passive"))
      (node (ref "R122") (pin "2") (pinfunction "2_2") (pintype "passive"))
      (node (ref "U32") (pin "5") (pinfunction "MODE_5") (pintype "passive"))
    )
    (net (code "58") (name "Net-(U32-PDC)") (class "Default")
      (node (ref "C66") (pin "2") (pinfunction "2_2") (pintype "passive"))
      (node (ref "R123") (pin "1") (pinfunction "1_1") (pintype "passive"))
      (node (ref "U32") (pin "7") (pinfunction "PDC_7") (pintype "passive"))
    )
    (net (code "59") (name "Net-(U32-RCT)") (class "Default")
      (node (ref "C65") (pin "2") (pinfunction "2_2") (pintype "passive"))
      (node (ref "R119") (pin "2") (pinfunction "2_2") (pintype "passive"))
      (node (ref "R125") (pin "2") (pinfunction "2_2") (pintype "passive"))
      (node (ref "U32") (pin "14") (pinfunction "RCT_14") (pintype "passive"))
    )
    (net (code "60") (name "Net-(U32-VIN)") (class "Default")
      (node (ref "R121") (pin "1") (pinfunction "1_1") (pintype "passive"))
      (node (ref "U32") (pin "3") (pinfunction "VIN_3") (pintype "power_in"))
    )
    (net (code "61") (name "Net-(U33-GOUT)") (class "Default")
      (node (ref "R132") (pin "2") (pinfunction "2_2") (pintype "passive"))
      (node (ref "U33") (pin "10") (pinfunction "GOUT_10") (pintype "output"))
    )
    (net (code "62") (name "Net-(U33-MODE)") (class "Default")
      (node (ref "R126") (pin "1") (pinfunction "1_1") (pintype "passive"))
      (node (ref "R130") (pin "2") (pinfunction "2_2") (pintype "passive"))
      (node (ref "U33") (pin "5") (pinfunction "MODE_5") (pintype "passive"))
    )
    (net (code "63") (name "Net-(U33-PDC)") (class "Default")
      (node (ref "C69") (pin "2") (pinfunction "2_2") (pintype "passive"))
      (node (ref "R131") (pin "1") (pinfunction "1_1") (pintype "passive"))
      (node (ref "U33") (pin "7") (pinfunction "PDC_7") (pintype "passive"))
    )
    (net (code "64") (name "Net-(U33-RCT)") (class "Default")
      (node (ref "C68") (pin "2") (pinfunction "2_2") (pintype "passive"))
      (node (ref "R127") (pin "2") (pinfunction "2_2") (pintype "passive"))
      (node (ref "R133") (pin "2") (pinfunction "2_2") (pintype "passive"))
      (node (ref "U33") (pin "14") (pinfunction "RCT_14") (pintype "passive"))
    )
    (net (code "65") (name "Net-(U33-VIN)") (class "Default")
      (node (ref "R129") (pin "1") (pinfunction "1_1") (pintype "passive"))
      (node (ref "U33") (pin "3") (pinfunction "VIN_3") (pintype "power_in"))
    )
    (net (code "68") (name "POW") (class "Default")
      (node (ref "R58") (pin "1") (pinfunction "1_1") (pintype "passive"))
    )
  )
)
